# mcuB.net
KiCad netlist of a schematic drawn in Altium Designer
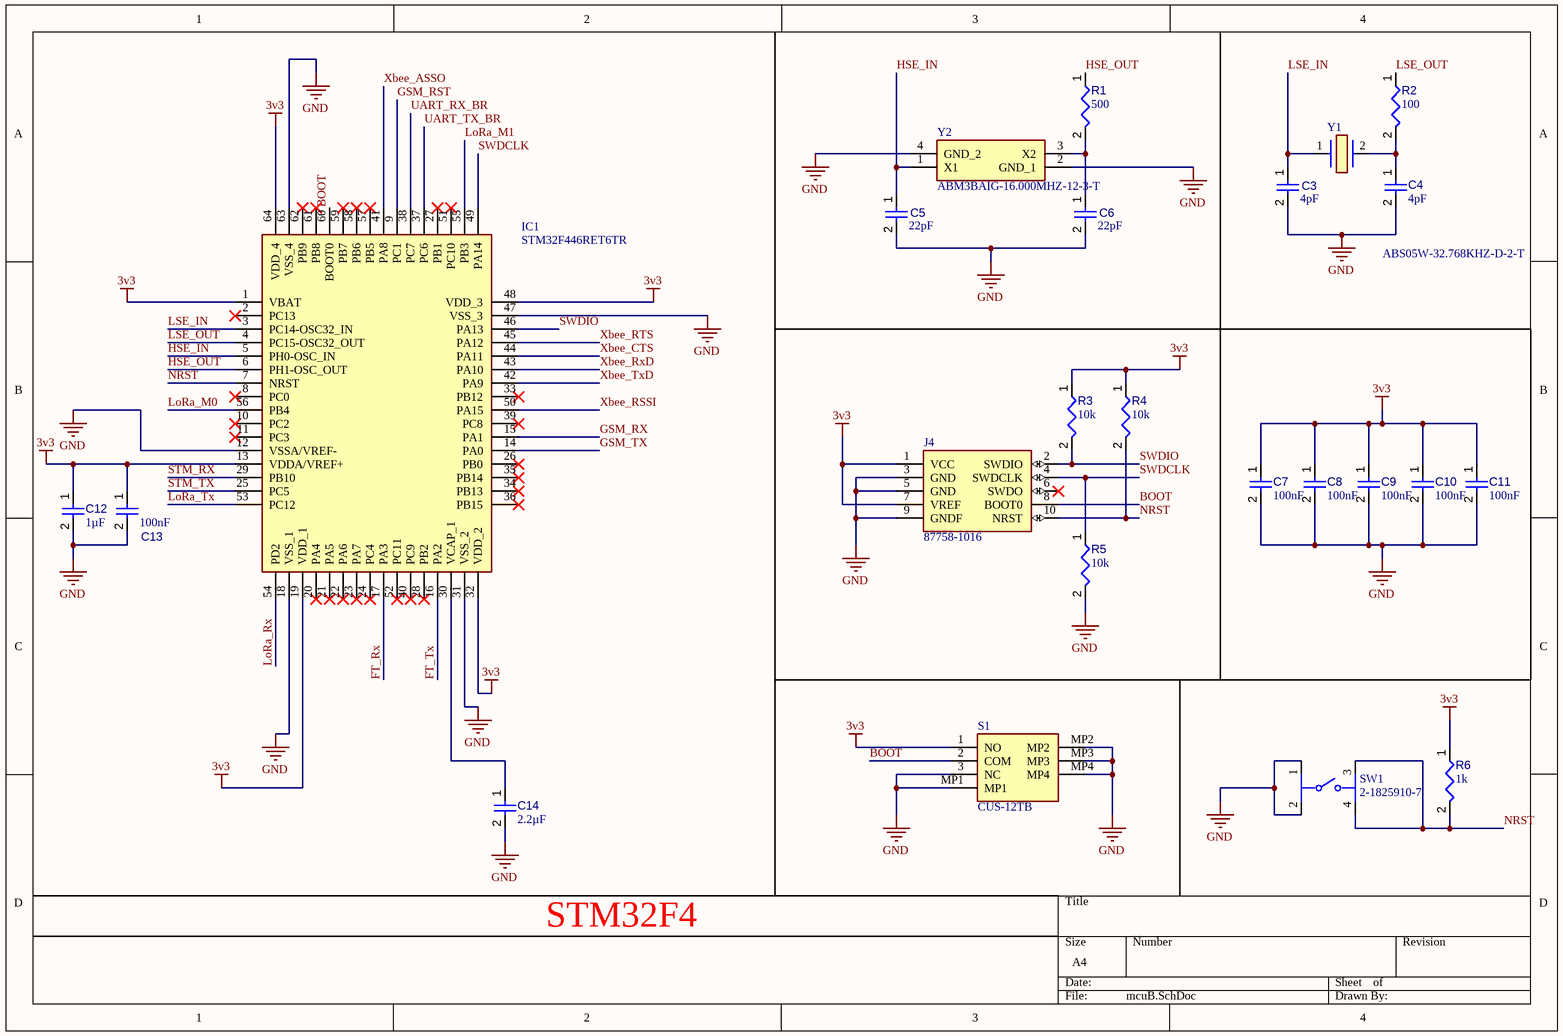
[diagram p0: mcuB.SchDoc]

(export (version "E")
  (design (tool "Eeschema 10.0.6"))
  (components
    (comp (ref "C3")
      (value "4pF")
      (footprint "CAPC1608X90X40LL10T20")
      (description "Chip Capacitor, 1 uF, +/- 10%, 25 V, 0603 (1608 Metric)")
      (fields (field (name "TOLERANCE") "10%") (field (name "Comment") "Capacitor 1 uF +/- 10% 25 V 0603"))
      (libsource (lib "Shlok Sharma") (part "CAP-NP-2"))
    )
    (comp (ref "C4")
      (value "4pF")
      (footprint "CAPC1608X90X40LL10T20")
      (description "Chip Capacitor, 1 uF, +/- 10%, 25 V, 0603 (1608 Metric)")
      (fields (field (name "TOLERANCE") "10%") (field (name "Comment") "Capacitor 1 uF +/- 10% 25 V 0603"))
      (libsource (lib "Shlok Sharma") (part "CAP-NP-2"))
    )
    (comp (ref "C5")
      (value "22pF")
      (footprint "CAPC1608X90X40LL10T20")
      (description "Chip Capacitor, 1 uF, +/- 10%, 25 V, 0603 (1608 Metric)")
      (fields (field (name "TOLERANCE") "10%") (field (name "Comment") "Capacitor 1 uF +/- 10% 25 V 0603"))
      (libsource (lib "Shlok Sharma") (part "CAP-NP-2"))
    )
    (comp (ref "C6")
      (value "22pF")
      (footprint "CAPC1608X90X40LL10T20")
      (description "Chip Capacitor, 1 uF, +/- 10%, 25 V, 0603 (1608 Metric)")
      (fields (field (name "TOLERANCE") "10%") (field (name "Comment") "Capacitor 1 uF +/- 10% 25 V 0603"))
      (libsource (lib "Shlok Sharma") (part "CAP-NP-2"))
    )
    (comp (ref "C7")
      (value "100nF")
      (footprint "CAPC1608X90X40NL10T20")
      (description "Chip Capacitor, 100 nF, +/- 10%, 50 V, 0603 (1608 Metric)")
      (fields (field (name "TOLERANCE") "10%") (field (name "Comment") "Capacitor 100 nF +/-10% 50 V 0603"))
      (libsource (lib "Shlok Sharma") (part "CAP-NP-2"))
    )
    (comp (ref "C8")
      (value "100nF")
      (footprint "CAPC1608X90X40NL10T20")
      (description "Chip Capacitor, 100 nF, +/- 10%, 50 V, 0603 (1608 Metric)")
      (fields (field (name "TOLERANCE") "10%") (field (name "Comment") "Capacitor 100 nF +/-10% 50 V 0603"))
      (libsource (lib "Shlok Sharma") (part "CAP-NP-2"))
    )
    (comp (ref "C9")
      (value "100nF")
      (footprint "CAPC1608X90X40NL10T20")
      (description "Chip Capacitor, 100 nF, +/- 10%, 50 V, 0603 (1608 Metric)")
      (fields (field (name "TOLERANCE") "10%") (field (name "Comment") "Capacitor 100 nF +/-10% 50 V 0603"))
      (libsource (lib "Shlok Sharma") (part "CAP-NP-2"))
    )
    (comp (ref "C10")
      (value "100nF")
      (footprint "CAPC1608X90X40NL10T20")
      (description "Chip Capacitor, 100 nF, +/- 10%, 50 V, 0603 (1608 Metric)")
      (fields (field (name "TOLERANCE") "10%") (field (name "Comment") "Capacitor 100 nF +/-10% 50 V 0603"))
      (libsource (lib "Shlok Sharma") (part "CAP-NP-2"))
    )
    (comp (ref "C11")
      (value "100nF")
      (footprint "CAPC1608X90X40NL10T20")
      (description "Chip Capacitor, 100 nF, +/- 10%, 50 V, 0603 (1608 Metric)")
      (fields (field (name "TOLERANCE") "10%") (field (name "Comment") "Capacitor 100 nF +/-10% 50 V 0603"))
      (libsource (lib "Shlok Sharma") (part "CAP-NP-2"))
    )
    (comp (ref "C12")
      (value "1µF")
      (footprint "CAPC2013X135X45NL10T25")
      (description "Chip Capacitor, 1 uF, +/- 10%, 50 V, 0805 (2012 Metric)")
      (fields (field (name "TOLERANCE") "10%") (field (name "Comment") "Capacitor 1 uF +/- 10% 50 V 0805"))
      (libsource (lib "Shlok Sharma") (part "CAP-NP-2"))
    )
    (comp (ref "C13")
      (value "100nF")
      (footprint "CAPC1608X90X40NL10T20")
      (description "Chip Capacitor, 100 nF, +/- 10%, 50 V, 0603 (1608 Metric)")
      (fields (field (name "TOLERANCE") "10%") (field (name "Comment") "Capacitor 100 nF +/-10% 50 V 0603"))
      (libsource (lib "Shlok Sharma") (part "CAP-NP-2"))
    )
    (comp (ref "C14")
      (value "2.2µF")
      (footprint "CAPC2013X135X45NL10T25")
      (description "Chip Capacitor, 1 uF, +/- 10%, 50 V, 0805 (2012 Metric)")
      (fields (field (name "TOLERANCE") "10%") (field (name "Comment") "Capacitor 1 uF +/- 10% 50 V 0805"))
      (libsource (lib "Shlok Sharma") (part "CAP-NP-2"))
    )
    (comp (ref "IC1")
      (value "STM32F446RET6TR")
      (footprint "SamacSys:QFP50P1200X1200X160-64N")
      (description "Integrated Circuit")
      (fields (field (name "MOUSER PART NUMBER") "511-STM32F446RET6TR"))
      (libsource (lib "*") (part "STM32F446RET6TR"))
    )
    (comp (ref "J4")
      (value "87758-1016")
      (footprint "SamacSys:HDRV10W75P200_2X5_990X400X595P")
      (description "Connector")
      (fields (field (name "MOUSER PART NUMBER") "538-87758-1016"))
      (libsource (lib "SamacSys") (part "87758-1016"))
    )
    (comp (ref "R1")
      (value "500")
      (footprint "RESC1608X55X25ML10T15")
      (description "Chip Resistor, 10 KOhm, +/- 1%, 01 W, -55 to 155 degC, 0603 (1608 Metric)")
      (fields (field (name "POWER") "100mW") (field (name "TOLERANCE") "1%"))
      (libsource (lib "Shlok Sharma") (part "RES-2"))
    )
    (comp (ref "R2")
      (value "100")
      (footprint "RESC1608X55X25ML10T15")
      (description "Chip Resistor, 10 KOhm, +/- 1%, 01 W, -55 to 155 degC, 0603 (1608 Metric)")
      (fields (field (name "POWER") "100mW") (field (name "TOLERANCE") "1%"))
      (libsource (lib "Shlok Sharma") (part "RES-2"))
    )
    (comp (ref "R3")
      (value "10k")
      (footprint "RESC1608X55X25ML10T15")
      (description "Chip Resistor, 10 KOhm, +/- 1%, 01 W, -55 to 155 degC, 0603 (1608 Metric)")
      (fields (field (name "POWER") "100mW") (field (name "TOLERANCE") "1%"))
      (libsource (lib "Shlok Sharma") (part "RES-2"))
    )
    (comp (ref "R4")
      (value "10k")
      (footprint "RESC1608X55X25ML10T15")
      (description "Chip Resistor, 10 KOhm, +/- 1%, 01 W, -55 to 155 degC, 0603 (1608 Metric)")
      (fields (field (name "POWER") "100mW") (field (name "TOLERANCE") "1%"))
      (libsource (lib "Shlok Sharma") (part "RES-2"))
    )
    (comp (ref "R5")
      (value "10k")
      (footprint "RESC1608X55X25ML10T15")
      (description "Chip Resistor, 10 KOhm, +/- 1%, 01 W, -55 to 155 degC, 0603 (1608 Metric)")
      (fields (field (name "POWER") "100mW") (field (name "TOLERANCE") "1%"))
      (libsource (lib "Shlok Sharma") (part "RES-2"))
    )
    (comp (ref "R6")
      (value "1k")
      (footprint "RESC1608X55X25ML10T15")
      (description "Chip Resistor, 10 KOhm, +/- 1%, 01 W, -55 to 155 degC, 0603 (1608 Metric)")
      (fields (field (name "POWER") "100mW") (field (name "TOLERANCE") "1%"))
      (libsource (lib "Shlok Sharma") (part "RES-2"))
    )
    (comp (ref "S1")
      (value "CUS-12TB")
      (footprint "SamacSys:CUS12TB")
      (description "Switch")
      (fields (field (name "MOUSER PART NUMBER") "229-CUS-12TB"))
      (libsource (lib "SamacSys") (part "CUS-12TB"))
    )
    (comp (ref "SW1")
      (value "2-1825910-7")
      (footprint "FP-2-1825910-7-MFG")
      (description "SWITCH TACTILE SPST-NO 0.05A 24V")
      (fields
        (field (name "MANUFACTURER") "TE Connectivity")
        (field (name "OCTOPART") "https://octopart.com/2-1825910-7-te+connectivity-42270510")
      )
      (libsource (lib "Altium Content Vault") (part "b8895f3f4cefb76e1819d2863dba89b"))
    )
    (comp (ref "Y1")
      (value "ABS05W-32.768KHZ-D-2-T")
      (footprint "SamacSys:ABS05W32768KHZD2T")
      (description "Crystal or Oscillator")
      (fields (field (name "MOUSER PART NUMBER") "815-ABS05W32.768KD2T"))
      (libsource (lib "*") (part "ABS05W-32.768KHZ-D-2-T"))
    )
    (comp (ref "Y2")
      (value "ABM3BAIG-16.000MHZ-12-3-T")
      (footprint "SamacSys:ABM3BAIG")
      (description "Crystal or Oscillator")
      (libsource (lib "*") (part "ABM3BAIG-16.000MHZ-12-3-T"))
    )
  )
  (nets
    (net (code "1") (name "/BOOT") (class "Default")
      (node (ref "IC1") (pin "60") (pinfunction "BOOT0_60") (pintype "passive"))
      (node (ref "J4") (pin "8") (pinfunction "BOOT0_8") (pintype "passive"))
      (node (ref "S1") (pin "2") (pinfunction "COM_2") (pintype "passive"))
    )
    (net (code "2") (name "/FT_Rx") (class "Default")
      (node (ref "IC1") (pin "17") (pinfunction "PA3_17") (pintype "passive"))
    )
    (net (code "3") (name "/FT_Tx") (class "Default")
      (node (ref "IC1") (pin "16") (pinfunction "PA2_16") (pintype "passive"))
    )
    (net (code "4") (name "/GSM_RST") (class "Default")
      (node (ref "IC1") (pin "9") (pinfunction "PC1_9") (pintype "passive"))
    )
    (net (code "5") (name "/GSM_RX") (class "Default")
      (node (ref "IC1") (pin "15") (pinfunction "PA1_15") (pintype "passive"))
    )
    (net (code "6") (name "/GSM_TX") (class "Default")
      (node (ref "IC1") (pin "14") (pinfunction "PA0_14") (pintype "passive"))
    )
    (net (code "7") (name "/HSE_IN") (class "Default")
      (node (ref "C5") (pin "1") (pinfunction "1_1") (pintype "passive"))
      (node (ref "IC1") (pin "5") (pinfunction "PH0-OSC_IN_5") (pintype "passive"))
      (node (ref "Y2") (pin "1") (pinfunction "X1_1") (pintype "passive"))
    )
    (net (code "8") (name "/HSE_OUT") (class "Default")
      (node (ref "IC1") (pin "6") (pinfunction "PH1-OSC_OUT_6") (pintype "passive"))
      (node (ref "R1") (pin "1") (pinfunction "1_1") (pintype "passive"))
    )
    (net (code "9") (name "/LSE_IN") (class "Default")
      (node (ref "C3") (pin "1") (pinfunction "1_1") (pintype "passive"))
      (node (ref "IC1") (pin "3") (pinfunction "PC14-OSC32_IN_3") (pintype "passive"))
      (node (ref "Y1") (pin "1") (pinfunction "1_1") (pintype "passive"))
    )
    (net (code "10") (name "/LSE_OUT") (class "Default")
      (node (ref "IC1") (pin "4") (pinfunction "PC15-OSC32_OUT_4") (pintype "passive"))
      (node (ref "R2") (pin "1") (pinfunction "1_1") (pintype "passive"))
    )
    (net (code "11") (name "/LoRa_M0") (class "Default")
      (node (ref "IC1") (pin "56") (pinfunction "PB4_56") (pintype "passive"))
    )
    (net (code "12") (name "/LoRa_M1") (class "Default")
      (node (ref "IC1") (pin "55") (pinfunction "PB3_55") (pintype "passive"))
    )
    (net (code "13") (name "/LoRa_Rx") (class "Default")
      (node (ref "IC1") (pin "54") (pinfunction "PD2_54") (pintype "passive"))
    )
    (net (code "14") (name "/LoRa_Tx") (class "Default")
      (node (ref "IC1") (pin "53") (pinfunction "PC12_53") (pintype "passive"))
    )
    (net (code "15") (name "/NRST") (class "Default")
      (node (ref "IC1") (pin "7") (pinfunction "NRST_7") (pintype "passive"))
      (node (ref "J4") (pin "10") (pinfunction "NRST_10") (pintype "bidirectional"))
      (node (ref "R4") (pin "2") (pinfunction "2_2") (pintype "passive"))
      (node (ref "R6") (pin "2") (pinfunction "2_2") (pintype "passive"))
      (node (ref "SW1") (pin "3") (pinfunction "3_3") (pintype "passive"))
      (node (ref "SW1") (pin "4") (pinfunction "4_4") (pintype "passive"))
    )
    (net (code "16") (name "/STM_RX") (class "Default")
      (node (ref "IC1") (pin "29") (pinfunction "PB10_29") (pintype "passive"))
    )
    (net (code "17") (name "/STM_TX") (class "Default")
      (node (ref "IC1") (pin "25") (pinfunction "PC5_25") (pintype "passive"))
    )
    (net (code "18") (name "/SWDCLK") (class "Default")
      (node (ref "IC1") (pin "49") (pinfunction "PA14_49") (pintype "passive"))
      (node (ref "J4") (pin "4") (pinfunction "SWDCLK_4") (pintype "bidirectional"))
      (node (ref "R5") (pin "1") (pinfunction "1_1") (pintype "passive"))
    )
    (net (code "19") (name "/SWDIO") (class "Default")
      (node (ref "IC1") (pin "46") (pinfunction "PA13_46") (pintype "passive"))
      (node (ref "J4") (pin "2") (pinfunction "SWDIO_2") (pintype "bidirectional"))
      (node (ref "R3") (pin "2") (pinfunction "2_2") (pintype "passive"))
    )
    (net (code "20") (name "/UART_RX_BR") (class "Default")
      (node (ref "IC1") (pin "38") (pinfunction "PC7_38") (pintype "passive"))
    )
    (net (code "21") (name "/UART_TX_BR") (class "Default")
      (node (ref "IC1") (pin "37") (pinfunction "PC6_37") (pintype "passive"))
    )
    (net (code "22") (name "/Xbee_ASSO") (class "Default")
      (node (ref "IC1") (pin "41") (pinfunction "PA8_41") (pintype "passive"))
    )
    (net (code "23") (name "/Xbee_CTS") (class "Default")
      (node (ref "IC1") (pin "44") (pinfunction "PA11_44") (pintype "passive"))
    )
    (net (code "24") (name "/Xbee_RSSI") (class "Default")
      (node (ref "IC1") (pin "50") (pinfunction "PA15_50") (pintype "passive"))
    )
    (net (code "25") (name "/Xbee_RTS") (class "Default")
      (node (ref "IC1") (pin "45") (pinfunction "PA12_45") (pintype "passive"))
    )
    (net (code "26") (name "/Xbee_RxD") (class "Default")
      (node (ref "IC1") (pin "43") (pinfunction "PA10_43") (pintype "passive"))
    )
    (net (code "27") (name "/Xbee_TxD") (class "Default")
      (node (ref "IC1") (pin "42") (pinfunction "PA9_42") (pintype "passive"))
    )
    (net (code "28") (name "3v3") (class "Default")
      (node (ref "C10") (pin "1") (pinfunction "1_1") (pintype "passive"))
      (node (ref "C11") (pin "1") (pinfunction "1_1") (pintype "passive"))
      (node (ref "C12") (pin "1") (pinfunction "1_1") (pintype "passive"))
      (node (ref "C13") (pin "1") (pinfunction "1_1") (pintype "passive"))
      (node (ref "C7") (pin "1") (pinfunction "1_1") (pintype "passive"))
      (node (ref "C8") (pin "1") (pinfunction "1_1") (pintype "passive"))
      (node (ref "C9") (pin "1") (pinfunction "1_1") (pintype "passive"))
      (node (ref "IC1") (pin "1") (pinfunction "VBAT_1") (pintype "passive"))
      (node (ref "IC1") (pin "13") (pinfunction "VDDA/VREF+_13") (pintype "passive"))
      (node (ref "IC1") (pin "19") (pinfunction "VDD_1_19") (pintype "passive"))
      (node (ref "IC1") (pin "32") (pinfunction "VDD_2_32") (pintype "passive"))
      (node (ref "IC1") (pin "48") (pinfunction "VDD_3_48") (pintype "passive"))
      (node (ref "IC1") (pin "64") (pinfunction "VDD_4_64") (pintype "passive"))
      (node (ref "J4") (pin "1") (pinfunction "VCC_1") (pintype "passive"))
      (node (ref "J4") (pin "7") (pinfunction "VREF_7") (pintype "passive"))
      (node (ref "R3") (pin "1") (pinfunction "1_1") (pintype "passive"))
      (node (ref "R4") (pin "1") (pinfunction "1_1") (pintype "passive"))
      (node (ref "R6") (pin "1") (pinfunction "1_1") (pintype "passive"))
      (node (ref "S1") (pin "1") (pinfunction "NO_1") (pintype "passive"))
    )
    (net (code "29") (name "GND") (class "Default")
      (node (ref "C10") (pin "2") (pinfunction "2_2") (pintype "passive"))
      (node (ref "C11") (pin "2") (pinfunction "2_2") (pintype "passive"))
      (node (ref "C12") (pin "2") (pinfunction "2_2") (pintype "passive"))
      (node (ref "C13") (pin "2") (pinfunction "2_2") (pintype "passive"))
      (node (ref "C14") (pin "2") (pinfunction "2_2") (pintype "passive"))
      (node (ref "C3") (pin "2") (pinfunction "2_2") (pintype "passive"))
      (node (ref "C4") (pin "2") (pinfunction "2_2") (pintype "passive"))
      (node (ref "C5") (pin "2") (pinfunction "2_2") (pintype "passive"))
      (node (ref "C6") (pin "2") (pinfunction "2_2") (pintype "passive"))
      (node (ref "C7") (pin "2") (pinfunction "2_2") (pintype "passive"))
      (node (ref "C8") (pin "2") (pinfunction "2_2") (pintype "passive"))
      (node (ref "C9") (pin "2") (pinfunction "2_2") (pintype "passive"))
      (node (ref "IC1") (pin "12") (pinfunction "VSSA/VREF-_12") (pintype "passive"))
      (node (ref "IC1") (pin "18") (pinfunction "VSS_1_18") (pintype "passive"))
      (node (ref "IC1") (pin "31") (pinfunction "VSS_2_31") (pintype "passive"))
      (node (ref "IC1") (pin "47") (pinfunction "VSS_3_47") (pintype "passive"))
      (node (ref "IC1") (pin "63") (pinfunction "VSS_4_63") (pintype "passive"))
      (node (ref "J4") (pin "3") (pinfunction "GND_3") (pintype "passive"))
      (node (ref "J4") (pin "5") (pinfunction "GND_5") (pintype "passive"))
      (node (ref "J4") (pin "9") (pinfunction "GNDF_9") (pintype "passive"))
      (node (ref "R5") (pin "2") (pinfunction "2_2") (pintype "passive"))
      (node (ref "S1") (pin "3") (pinfunction "NC_3") (pintype "passive"))
      (node (ref "S1") (pin "MP1") (pinfunction "MP1_MP1") (pintype "passive"))
      (node (ref "S1") (pin "MP2") (pinfunction "MP2_MP2") (pintype "passive"))
      (node (ref "S1") (pin "MP3") (pinfunction "MP3_MP3") (pintype "passive"))
      (node (ref "S1") (pin "MP4") (pinfunction "MP4_MP4") (pintype "passive"))
      (node (ref "SW1") (pin "1") (pinfunction "1_1") (pintype "passive"))
      (node (ref "SW1") (pin "2") (pinfunction "2_2") (pintype "passive"))
      (node (ref "Y2") (pin "2") (pinfunction "GND_1_2") (pintype "passive"))
      (node (ref "Y2") (pin "4") (pinfunction "GND_2_4") (pintype "passive"))
    )
    (net (code "30") (name "Net-(C4-Pad1)") (class "Default")
      (node (ref "C4") (pin "1") (pinfunction "1_1") (pintype "passive"))
      (node (ref "R2") (pin "2") (pinfunction "2_2") (pintype "passive"))
      (node (ref "Y1") (pin "2") (pinfunction "2_2") (pintype "passive"))
    )
    (net (code "31") (name "Net-(IC1-VCAP_1)") (class "Default")
      (node (ref "C14") (pin "1") (pinfunction "1_1") (pintype "passive"))
      (node (ref "IC1") (pin "30") (pinfunction "VCAP_1_30") (pintype "passive"))
    )
    (net (code "32") (name "Net-(Y2-X2)") (class "Default")
      (node (ref "C6") (pin "1") (pinfunction "1_1") (pintype "passive"))
      (node (ref "R1") (pin "2") (pinfunction "2_2") (pintype "passive"))
      (node (ref "Y2") (pin "3") (pinfunction "X2_3") (pintype "passive"))
    )
    (net (code "33") (name "unconnected-(IC1-PA4-Pad20)") (class "Default")
      (node (ref "IC1") (pin "20") (pinfunction "PA4_20") (pintype "passive+no_connect"))
    )
    (net (code "34") (name "unconnected-(IC1-PA5-Pad21)") (class "Default")
      (node (ref "IC1") (pin "21") (pinfunction "PA5_21") (pintype "passive+no_connect"))
    )
    (net (code "35") (name "unconnected-(IC1-PA6-Pad22)") (class "Default")
      (node (ref "IC1") (pin "22") (pinfunction "PA6_22") (pintype "passive+no_connect"))
    )
    (net (code "36") (name "unconnected-(IC1-PA7-Pad23)") (class "Default")
      (node (ref "IC1") (pin "23") (pinfunction "PA7_23") (pintype "passive+no_connect"))
    )
    (net (code "37") (name "unconnected-(IC1-PB0-Pad26)") (class "Default")
      (node (ref "IC1") (pin "26") (pinfunction "PB0_26") (pintype "passive+no_connect"))
    )
    (net (code "38") (name "unconnected-(IC1-PB1-Pad27)") (class "Default")
      (node (ref "IC1") (pin "27") (pinfunction "PB1_27") (pintype "passive+no_connect"))
    )
    (net (code "39") (name "unconnected-(IC1-PB2-Pad28)") (class "Default")
      (node (ref "IC1") (pin "28") (pinfunction "PB2_28") (pintype "passive+no_connect"))
    )
    (net (code "40") (name "unconnected-(IC1-PB5-Pad57)") (class "Default")
      (node (ref "IC1") (pin "57") (pinfunction "PB5_57") (pintype "passive+no_connect"))
    )
    (net (code "41") (name "unconnected-(IC1-PB6-Pad58)") (class "Default")
      (node (ref "IC1") (pin "58") (pinfunction "PB6_58") (pintype "passive+no_connect"))
    )
    (net (code "42") (name "unconnected-(IC1-PB7-Pad59)") (class "Default")
      (node (ref "IC1") (pin "59") (pinfunction "PB7_59") (pintype "passive+no_connect"))
    )
    (net (code "43") (name "unconnected-(IC1-PB8-Pad61)") (class "Default")
      (node (ref "IC1") (pin "61") (pinfunction "PB8_61") (pintype "passive+no_connect"))
    )
    (net (code "44") (name "unconnected-(IC1-PB9-Pad62)") (class "Default")
      (node (ref "IC1") (pin "62") (pinfunction "PB9_62") (pintype "passive+no_connect"))
    )
    (net (code "45") (name "unconnected-(IC1-PB12-Pad33)") (class "Default")
      (node (ref "IC1") (pin "33") (pinfunction "PB12_33") (pintype "passive+no_connect"))
    )
    (net (code "46") (name "unconnected-(IC1-PB13-Pad34)") (class "Default")
      (node (ref "IC1") (pin "34") (pinfunction "PB13_34") (pintype "passive+no_connect"))
    )
    (net (code "47") (name "unconnected-(IC1-PB14-Pad35)") (class "Default")
      (node (ref "IC1") (pin "35") (pinfunction "PB14_35") (pintype "passive+no_connect"))
    )
    (net (code "48") (name "unconnected-(IC1-PB15-Pad36)") (class "Default")
      (node (ref "IC1") (pin "36") (pinfunction "PB15_36") (pintype "passive+no_connect"))
    )
    (net (code "49") (name "unconnected-(IC1-PC0-Pad8)") (class "Default")
      (node (ref "IC1") (pin "8") (pinfunction "PC0_8") (pintype "passive+no_connect"))
    )
    (net (code "50") (name "unconnected-(IC1-PC2-Pad10)") (class "Default")
      (node (ref "IC1") (pin "10") (pinfunction "PC2_10") (pintype "passive+no_connect"))
    )
    (net (code "51") (name "unconnected-(IC1-PC3-Pad11)") (class "Default")
      (node (ref "IC1") (pin "11") (pinfunction "PC3_11") (pintype "passive+no_connect"))
    )
    (net (code "52") (name "unconnected-(IC1-PC4-Pad24)") (class "Default")
      (node (ref "IC1") (pin "24") (pinfunction "PC4_24") (pintype "passive+no_connect"))
    )
    (net (code "53") (name "unconnected-(IC1-PC8-Pad39)") (class "Default")
      (node (ref "IC1") (pin "39") (pinfunction "PC8_39") (pintype "passive+no_connect"))
    )
    (net (code "54") (name "unconnected-(IC1-PC9-Pad40)") (class "Default")
      (node (ref "IC1") (pin "40") (pinfunction "PC9_40") (pintype "passive+no_connect"))
    )
    (net (code "55") (name "unconnected-(IC1-PC10-Pad51)") (class "Default")
      (node (ref "IC1") (pin "51") (pinfunction "PC10_51") (pintype "passive+no_connect"))
    )
    (net (code "56") (name "unconnected-(IC1-PC11-Pad52)") (class "Default")
      (node (ref "IC1") (pin "52") (pinfunction "PC11_52") (pintype "passive+no_connect"))
    )
    (net (code "57") (name "unconnected-(IC1-PC13-Pad2)") (class "Default")
      (node (ref "IC1") (pin "2") (pinfunction "PC13_2") (pintype "passive+no_connect"))
    )
    (net (code "58") (name "unconnected-(J4-SWDO-Pad6)") (class "Default")
      (node (ref "J4") (pin "6") (pinfunction "SWDO_6") (pintype "bidirectional+no_connect"))
    )
  )
)
